# design.net
KiCad netlist of a schematic drawn in Altium Designer
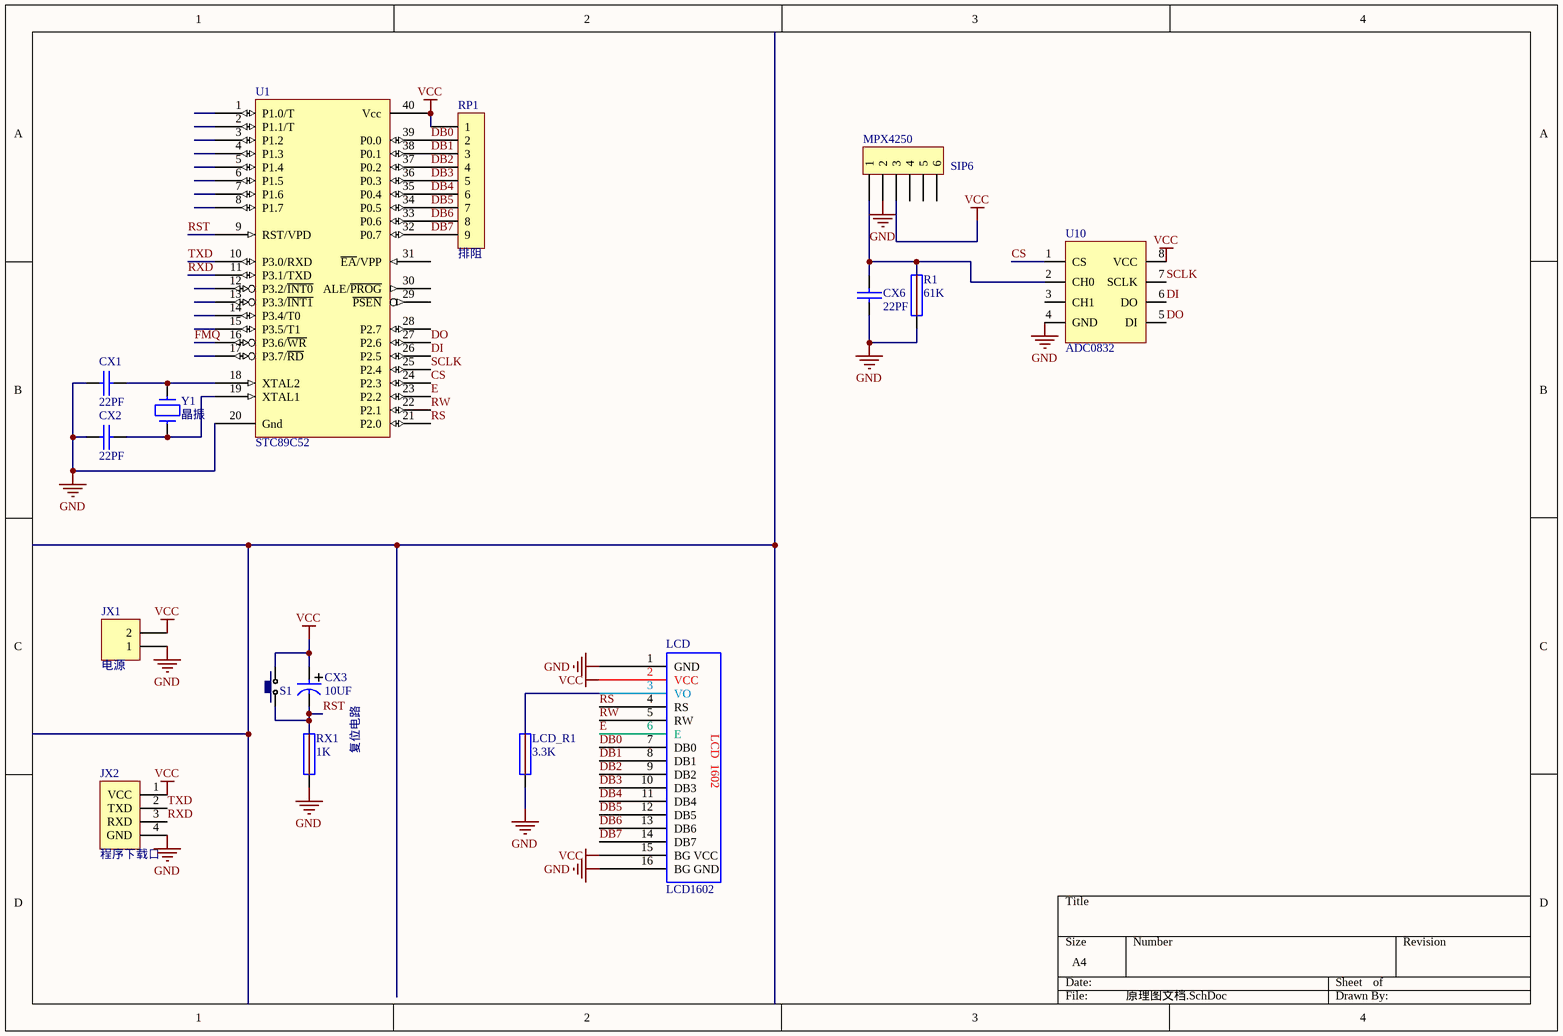
[diagram p0: 原理图文档.SchDoc]

(export (version "E")
  (design (tool "Eeschema 10.0.6"))
  (components
    (comp (ref "CX1") (value "22PF") (footprint "电容22") (libsource (lib "BBBBBBBBBBBB") (part "电容22PF")))
    (comp (ref "CX2") (value "22PF") (footprint "电容22") (libsource (lib "BBBBBBBBBBBB") (part "电容22PF")))
    (comp (ref "CX3") (value "10UF") (footprint "电容10") (libsource (lib "BBBBBBBBBBBB") (part "电容10UF")))
    (comp (ref "CX6") (value "22PF") (footprint "电容22") (libsource (lib "BBBBBBBBBBBB") (part "电容22PF")))
    (comp (ref "JX1") (value "电源") (footprint "端子") (libsource (lib "BBBBBBBBBBBB") (part "端子")))
    (comp (ref "JX2") (value "程序下载口") (footprint "ASIP4") (libsource (lib "BBBBBBBBBBBB") (part "程序下载口")))
    (comp (ref "LCD") (value "LCD1602") (footprint "ALCD1602") (libsource (lib "2019.6.7") (part "LCD1602")))
    (comp (ref "LCD_R1") (value "3.3K") (footprint "电阻") (libsource (lib "2019.9.8") (part "电阻1K")))
    (comp (ref "MPX4250") (value "SIP6") (footprint "ASIP6") (libsource (lib "2019.9.8") (part "SIP6")))
    (comp (ref "R1") (value "61K") (footprint "电阻") (libsource (lib "2019.9.8") (part "电阻1K")))
    (comp (ref "RP1") (value "排阻") (footprint "ASIP9") (libsource (lib "2019.6.7") (part "排阻")))
    (comp (ref "RX1") (value "1K") (footprint "电阻0.3") (libsource (lib "BBBBBBBBBBBB") (part "电阻1K")))
    (comp (ref "S1") (value "按键") (footprint "按键") (libsource (lib "2019.9.8") (part "按键")))
    (comp (ref "U1") (value "STC89C52") (footprint "ADIP40") (libsource (lib "BBBBBBBBBBBB") (part "单片机")))
    (comp (ref "U10") (value "ADC0832") (footprint "ADIP8") (libsource (lib "2019.6.15") (part "ADC0832")))
    (comp (ref "Y1") (value "晶振") (footprint "晶振") (libsource (lib "BBBBBBBBBBBB") (part "晶振")))
  )
  (nets
    (net (code "1") (name "/CS") (class "Default")
      (node (ref "U1") (pin "24") (pinfunction "P2.3_24") (pintype "bidirectional"))
      (node (ref "U10") (pin "1") (pinfunction "CS_1") (pintype "passive"))
    )
    (net (code "2") (name "/DB0") (class "Default")
      (node (ref "LCD") (pin "7") (pinfunction "DB0_7") (pintype "passive"))
      (node (ref "RP1") (pin "2") (pinfunction "2_2") (pintype "passive"))
      (node (ref "U1") (pin "39") (pinfunction "P0.0_39") (pintype "bidirectional"))
    )
    (net (code "3") (name "/DB1") (class "Default")
      (node (ref "LCD") (pin "8") (pinfunction "DB1_8") (pintype "passive"))
      (node (ref "RP1") (pin "3") (pinfunction "3_3") (pintype "passive"))
      (node (ref "U1") (pin "38") (pinfunction "P0.1_38") (pintype "bidirectional"))
    )
    (net (code "4") (name "/DB2") (class "Default")
      (node (ref "LCD") (pin "9") (pinfunction "DB2_9") (pintype "passive"))
      (node (ref "RP1") (pin "4") (pinfunction "4_4") (pintype "passive"))
      (node (ref "U1") (pin "37") (pinfunction "P0.2_37") (pintype "bidirectional"))
    )
    (net (code "5") (name "/DB3") (class "Default")
      (node (ref "LCD") (pin "10") (pinfunction "DB3_10") (pintype "passive"))
      (node (ref "RP1") (pin "5") (pinfunction "5_5") (pintype "passive"))
      (node (ref "U1") (pin "36") (pinfunction "P0.3_36") (pintype "bidirectional"))
    )
    (net (code "6") (name "/DB4") (class "Default")
      (node (ref "LCD") (pin "11") (pinfunction "DB4_11") (pintype "passive"))
      (node (ref "RP1") (pin "6") (pinfunction "6_6") (pintype "passive"))
      (node (ref "U1") (pin "35") (pinfunction "P0.4_35") (pintype "bidirectional"))
    )
    (net (code "7") (name "/DB5") (class "Default")
      (node (ref "LCD") (pin "12") (pinfunction "DB5_12") (pintype "passive"))
      (node (ref "RP1") (pin "7") (pinfunction "7_7") (pintype "passive"))
      (node (ref "U1") (pin "34") (pinfunction "P0.5_34") (pintype "bidirectional"))
    )
    (net (code "8") (name "/DB6") (class "Default")
      (node (ref "LCD") (pin "13") (pinfunction "DB6_13") (pintype "passive"))
      (node (ref "RP1") (pin "8") (pinfunction "8_8") (pintype "passive"))
      (node (ref "U1") (pin "33") (pinfunction "P0.6_33") (pintype "bidirectional"))
    )
    (net (code "9") (name "/DB7") (class "Default")
      (node (ref "LCD") (pin "14") (pinfunction "DB7_14") (pintype "passive"))
      (node (ref "RP1") (pin "9") (pinfunction "9_9") (pintype "passive"))
      (node (ref "U1") (pin "32") (pinfunction "P0.7_32") (pintype "bidirectional"))
    )
    (net (code "10") (name "/DI") (class "Default")
      (node (ref "U1") (pin "26") (pinfunction "P2.5_26") (pintype "bidirectional"))
      (node (ref "U10") (pin "6") (pinfunction "DO_6") (pintype "passive"))
    )
    (net (code "11") (name "/DO") (class "Default")
      (node (ref "U1") (pin "27") (pinfunction "P2.6_27") (pintype "bidirectional"))
      (node (ref "U10") (pin "5") (pinfunction "DI_5") (pintype "passive"))
    )
    (net (code "12") (name "/E") (class "Default")
      (node (ref "LCD") (pin "6") (pinfunction "E_6") (pintype "passive"))
      (node (ref "U1") (pin "23") (pinfunction "P2.2_23") (pintype "bidirectional"))
    )
    (net (code "13") (name "/FMQ") (class "Default")
      (node (ref "U1") (pin "16") (pinfunction "P3.6/~{WR}_16") (pintype "bidirectional"))
    )
    (net (code "14") (name "/RS") (class "Default")
      (node (ref "LCD") (pin "4") (pinfunction "RS_4") (pintype "passive"))
      (node (ref "U1") (pin "21") (pinfunction "P2.0_21") (pintype "bidirectional"))
    )
    (net (code "15") (name "/RST") (class "Default")
      (node (ref "CX3") (pin "2") (pinfunction "2_2") (pintype "passive"))
      (node (ref "RX1") (pin "2") (pinfunction "2_2") (pintype "passive"))
      (node (ref "S1") (pin "1") (pinfunction "1_1") (pintype "passive"))
      (node (ref "U1") (pin "9") (pinfunction "RST/VPD_9") (pintype "input"))
    )
    (net (code "16") (name "/RW") (class "Default")
      (node (ref "LCD") (pin "5") (pinfunction "RW_5") (pintype "passive"))
      (node (ref "U1") (pin "22") (pinfunction "P2.1_22") (pintype "bidirectional"))
    )
    (net (code "17") (name "/RXD") (class "Default")
      (node (ref "JX2") (pin "3") (pinfunction "RXD_3") (pintype "passive"))
      (node (ref "U1") (pin "11") (pinfunction "P3.1/TXD_11") (pintype "bidirectional"))
    )
    (net (code "18") (name "/SCLK") (class "Default")
      (node (ref "U1") (pin "25") (pinfunction "P2.4_25") (pintype "bidirectional"))
      (node (ref "U10") (pin "7") (pinfunction "SCLK_7") (pintype "passive"))
    )
    (net (code "19") (name "/TXD") (class "Default")
      (node (ref "JX2") (pin "2") (pinfunction "TXD_2") (pintype "passive"))
      (node (ref "U1") (pin "10") (pinfunction "P3.0/RXD_10") (pintype "bidirectional"))
    )
    (net (code "20") (name "GND") (class "Default")
      (node (ref "CX1") (pin "1") (pinfunction "1_1") (pintype "passive"))
      (node (ref "CX2") (pin "1") (pinfunction "1_1") (pintype "passive"))
      (node (ref "CX6") (pin "1") (pinfunction "1_1") (pintype "passive"))
      (node (ref "JX1") (pin "1") (pinfunction "1_1") (pintype "passive"))
      (node (ref "JX2") (pin "4") (pinfunction "GND_4") (pintype "passive"))
      (node (ref "LCD") (pin "1") (pinfunction "GND_1") (pintype "passive"))
      (node (ref "LCD") (pin "16") (pinfunction "BG_GND_16") (pintype "passive"))
      (node (ref "LCD_R1") (pin "1") (pinfunction "1_1") (pintype "passive"))
      (node (ref "MPX4250") (pin "2") (pinfunction "2_2") (pintype "passive"))
      (node (ref "R1") (pin "1") (pinfunction "1_1") (pintype "passive"))
      (node (ref "RX1") (pin "1") (pinfunction "1_1") (pintype "passive"))
      (node (ref "U1") (pin "20") (pinfunction "Gnd_20") (pintype "power_in"))
      (node (ref "U10") (pin "4") (pinfunction "GND_4") (pintype "passive"))
    )
    (net (code "21") (name "Net-(LCD-VO)") (class "Default")
      (node (ref "LCD") (pin "3") (pinfunction "VO_3") (pintype "passive"))
      (node (ref "LCD_R1") (pin "2") (pinfunction "2_2") (pintype "passive"))
    )
    (net (code "22") (name "Net-(U1-XTAL1)") (class "Default")
      (node (ref "CX2") (pin "2") (pinfunction "2_2") (pintype "passive"))
      (node (ref "U1") (pin "19") (pinfunction "XTAL1_19") (pintype "input"))
      (node (ref "Y1") (pin "1") (pinfunction "1_1") (pintype "passive"))
    )
    (net (code "23") (name "Net-(U1-XTAL2)") (class "Default")
      (node (ref "CX1") (pin "2") (pinfunction "2_2") (pintype "passive"))
      (node (ref "U1") (pin "18") (pinfunction "XTAL2_18") (pintype "input"))
      (node (ref "Y1") (pin "2") (pinfunction "2_2") (pintype "passive"))
    )
    (net (code "24") (name "Net-(U10-CH0)") (class "Default")
      (node (ref "CX6") (pin "2") (pinfunction "2_2") (pintype "passive"))
      (node (ref "MPX4250") (pin "1") (pinfunction "1_1") (pintype "passive"))
      (node (ref "R1") (pin "2") (pinfunction "2_2") (pintype "passive"))
      (node (ref "U10") (pin "2") (pinfunction "CH0_2") (pintype "passive"))
    )
    (net (code "25") (name "VCC") (class "Default")
      (node (ref "CX3") (pin "1") (pinfunction "1_1") (pintype "passive"))
      (node (ref "JX1") (pin "2") (pinfunction "2_2") (pintype "passive"))
      (node (ref "JX2") (pin "1") (pinfunction "VCC_1") (pintype "passive"))
      (node (ref "LCD") (pin "15") (pinfunction "BG_VCC_15") (pintype "passive"))
      (node (ref "LCD") (pin "2") (pinfunction "VCC_2") (pintype "passive"))
      (node (ref "MPX4250") (pin "3") (pinfunction "3_3") (pintype "passive"))
      (node (ref "RP1") (pin "1") (pinfunction "1_1") (pintype "passive"))
      (node (ref "S1") (pin "2") (pinfunction "2_2") (pintype "passive"))
      (node (ref "U1") (pin "40") (pinfunction "Vcc_40") (pintype "power_in"))
      (node (ref "U10") (pin "8") (pinfunction "VCC_8") (pintype "passive"))
    )
    (net (code "26") (name "unconnected-(MPX4250-Pad4)") (class "Default")
      (node (ref "MPX4250") (pin "4") (pinfunction "4_4") (pintype "passive"))
    )
    (net (code "27") (name "unconnected-(MPX4250-Pad5)") (class "Default")
      (node (ref "MPX4250") (pin "5") (pinfunction "5_5") (pintype "passive"))
    )
    (net (code "28") (name "unconnected-(MPX4250-Pad6)") (class "Default")
      (node (ref "MPX4250") (pin "6") (pinfunction "6_6") (pintype "passive"))
    )
    (net (code "29") (name "unconnected-(U1-ALE{slash}~{PROG}-Pad30)") (class "Default")
      (node (ref "U1") (pin "30") (pinfunction "ALE/~{PROG}_30") (pintype "output"))
    )
    (net (code "30") (name "unconnected-(U1-P1.0{slash}T-Pad1)") (class "Default")
      (node (ref "U1") (pin "1") (pinfunction "P1.0/T_1") (pintype "bidirectional"))
    )
    (net (code "31") (name "unconnected-(U1-P1.1{slash}T-Pad2)") (class "Default")
      (node (ref "U1") (pin "2") (pinfunction "P1.1/T_2") (pintype "bidirectional"))
    )
    (net (code "32") (name "unconnected-(U1-P1.2-Pad3)") (class "Default")
      (node (ref "U1") (pin "3") (pinfunction "P1.2_3") (pintype "bidirectional"))
    )
    (net (code "33") (name "unconnected-(U1-P1.3-Pad4)") (class "Default")
      (node (ref "U1") (pin "4") (pinfunction "P1.3_4") (pintype "bidirectional"))
    )
    (net (code "34") (name "unconnected-(U1-P1.4-Pad5)") (class "Default")
      (node (ref "U1") (pin "5") (pinfunction "P1.4_5") (pintype "bidirectional"))
    )
    (net (code "35") (name "unconnected-(U1-P1.5-Pad6)") (class "Default")
      (node (ref "U1") (pin "6") (pinfunction "P1.5_6") (pintype "bidirectional"))
    )
    (net (code "36") (name "unconnected-(U1-P1.6-Pad7)") (class "Default")
      (node (ref "U1") (pin "7") (pinfunction "P1.6_7") (pintype "bidirectional"))
    )
    (net (code "37") (name "unconnected-(U1-P1.7-Pad8)") (class "Default")
      (node (ref "U1") (pin "8") (pinfunction "P1.7_8") (pintype "bidirectional"))
    )
    (net (code "38") (name "unconnected-(U1-P2.7-Pad28)") (class "Default")
      (node (ref "U1") (pin "28") (pinfunction "P2.7_28") (pintype "bidirectional"))
    )
    (net (code "39") (name "unconnected-(U1-P3.2{slash}~{INT0}-Pad12)") (class "Default")
      (node (ref "U1") (pin "12") (pinfunction "P3.2/~{INT0}_12") (pintype "bidirectional"))
    )
    (net (code "40") (name "unconnected-(U1-P3.3{slash}~{INT1}-Pad13)") (class "Default")
      (node (ref "U1") (pin "13") (pinfunction "P3.3/~{INT1}_13") (pintype "bidirectional"))
    )
    (net (code "41") (name "unconnected-(U1-P3.4{slash}T0-Pad14)") (class "Default")
      (node (ref "U1") (pin "14") (pinfunction "P3.4/T0_14") (pintype "bidirectional"))
    )
    (net (code "42") (name "unconnected-(U1-P3.5{slash}T1-Pad15)") (class "Default")
      (node (ref "U1") (pin "15") (pinfunction "P3.5/T1_15") (pintype "bidirectional"))
    )
    (net (code "43") (name "unconnected-(U1-P3.7{slash}~{RD}-Pad17)") (class "Default")
      (node (ref "U1") (pin "17") (pinfunction "P3.7/~{RD}_17") (pintype "bidirectional"))
    )
    (net (code "44") (name "unconnected-(U1-~{EA}{slash}VPP-Pad31)") (class "Default")
      (node (ref "U1") (pin "31") (pinfunction "~{EA}/VPP_31") (pintype "input"))
    )
    (net (code "45") (name "unconnected-(U1-~{PSEN}-Pad29)") (class "Default")
      (node (ref "U1") (pin "29") (pinfunction "~{PSEN}_29") (pintype "output"))
    )
    (net (code "46") (name "unconnected-(U10-CH1-Pad3)") (class "Default")
      (node (ref "U10") (pin "3") (pinfunction "CH1_3") (pintype "passive"))
    )
  )
)
